# bmsSlave_conn.net
KiCad netlist of a schematic drawn in Altium Designer
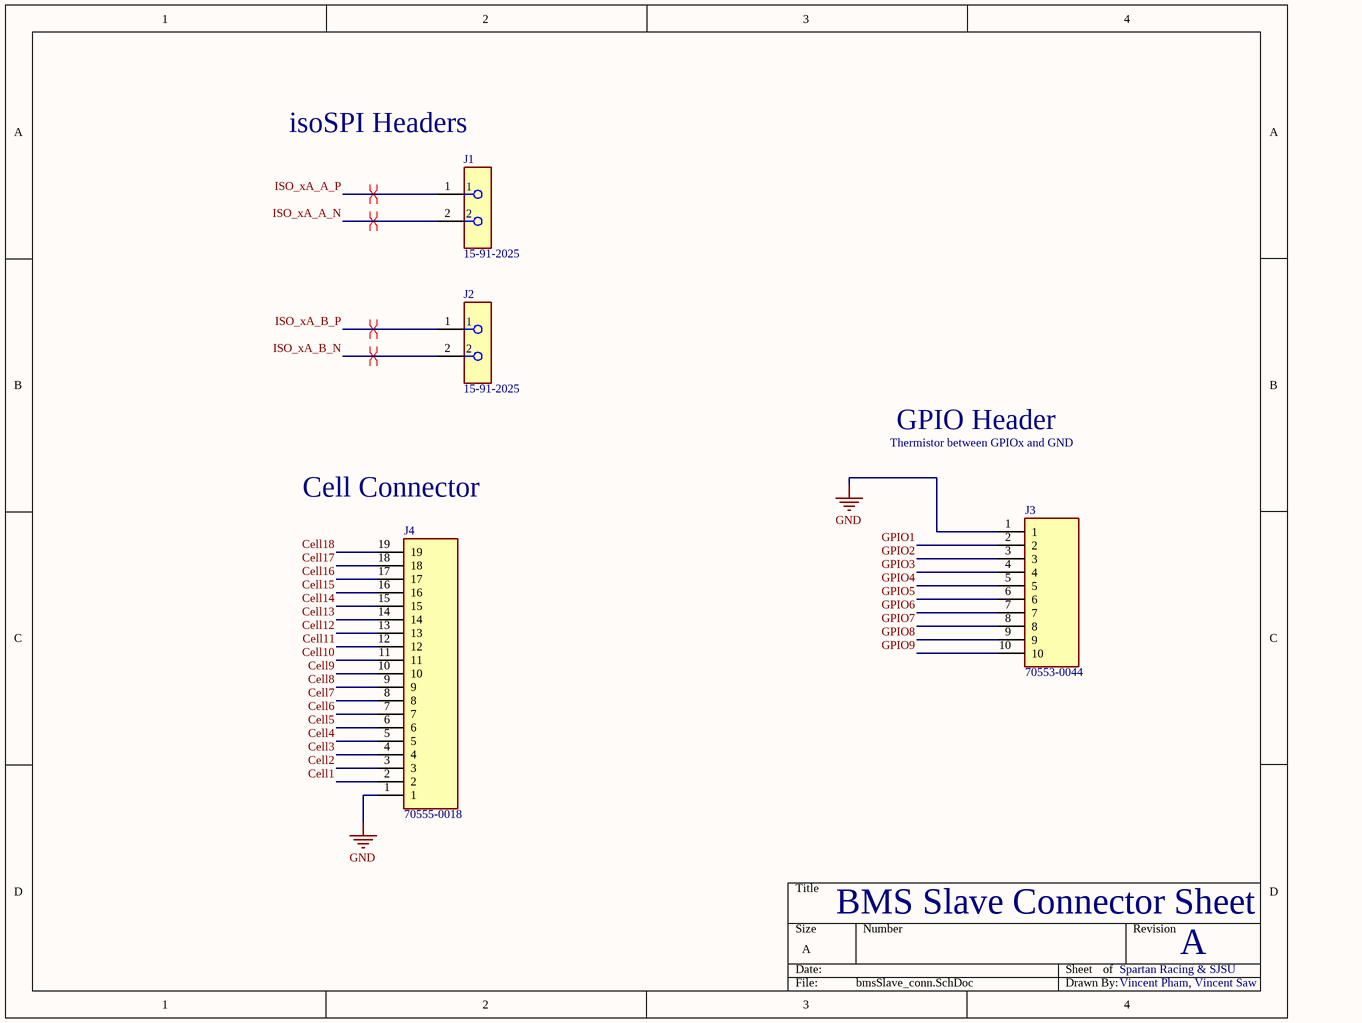
[diagram p0: bmsSlave_conn.SchDoc]

(export (version "E")
  (design (tool "Eeschema 10.0.6"))
  (components
    (comp (ref "J1")
      (value "15-91-2025")
      (footprint "FP-15-91-2025-MFG")
      (description "CONN HEADER SMD R/A 2POS 2.54MM")
      (libsource (lib "Altium Content Vault") (part "3ddab50f66188bb7952c54a1b76274c"))
    )
    (comp (ref "J2")
      (value "15-91-2025")
      (footprint "FP-15-91-2025-MFG")
      (description "CONN HEADER SMD R/A 2POS 2.54MM")
      (libsource (lib "Altium Content Vault") (part "3ddab50f66188bb7952c54a1b76274c"))
    )
    (comp (ref "J3")
      (value "70553-0044")
      (footprint "705550044")
      (description "Connector")
      (fields (field (name "MOUSER PART NUMBER") "538-70553-0044"))
      (libsource (lib "bmsSlave") (part "70553-0044"))
    )
    (comp (ref "J4")
      (value "70555-0018")
      (footprint "705550018")
      (description "Connector")
      (libsource (lib "bmsSlave") (part "70555-0018"))
    )
  )
  (nets
    (net (code "1") (name "/Cell1") (class "Default")
      (node (ref "J4") (pin "2") (pinfunction "2_2") (pintype "passive"))
    )
    (net (code "2") (name "/Cell2") (class "Default")
      (node (ref "J4") (pin "3") (pinfunction "3_3") (pintype "passive"))
    )
    (net (code "3") (name "/Cell3") (class "Default")
      (node (ref "J4") (pin "4") (pinfunction "4_4") (pintype "passive"))
    )
    (net (code "4") (name "/Cell4") (class "Default")
      (node (ref "J4") (pin "5") (pinfunction "5_5") (pintype "passive"))
    )
    (net (code "5") (name "/Cell5") (class "Default")
      (node (ref "J4") (pin "6") (pinfunction "6_6") (pintype "passive"))
    )
    (net (code "6") (name "/Cell6") (class "Default")
      (node (ref "J4") (pin "7") (pinfunction "7_7") (pintype "passive"))
    )
    (net (code "7") (name "/Cell7") (class "Default")
      (node (ref "J4") (pin "8") (pinfunction "8_8") (pintype "passive"))
    )
    (net (code "8") (name "/Cell8") (class "Default")
      (node (ref "J4") (pin "9") (pinfunction "9_9") (pintype "passive"))
    )
    (net (code "9") (name "/Cell9") (class "Default")
      (node (ref "J4") (pin "10") (pinfunction "10_10") (pintype "passive"))
    )
    (net (code "10") (name "/Cell10") (class "Default")
      (node (ref "J4") (pin "11") (pinfunction "11_11") (pintype "passive"))
    )
    (net (code "11") (name "/Cell11") (class "Default")
      (node (ref "J4") (pin "12") (pinfunction "12_12") (pintype "passive"))
    )
    (net (code "12") (name "/Cell12") (class "Default")
      (node (ref "J4") (pin "13") (pinfunction "13_13") (pintype "passive"))
    )
    (net (code "13") (name "/Cell13") (class "Default")
      (node (ref "J4") (pin "14") (pinfunction "14_14") (pintype "passive"))
    )
    (net (code "14") (name "/Cell14") (class "Default")
      (node (ref "J4") (pin "15") (pinfunction "15_15") (pintype "passive"))
    )
    (net (code "15") (name "/Cell15") (class "Default")
      (node (ref "J4") (pin "16") (pinfunction "16_16") (pintype "passive"))
    )
    (net (code "16") (name "/Cell16") (class "Default")
      (node (ref "J4") (pin "17") (pinfunction "17_17") (pintype "passive"))
    )
    (net (code "17") (name "/Cell17") (class "Default")
      (node (ref "J4") (pin "18") (pinfunction "18_18") (pintype "passive"))
    )
    (net (code "18") (name "/Cell18") (class "Default")
      (node (ref "J4") (pin "19") (pinfunction "19_19") (pintype "passive"))
    )
    (net (code "19") (name "/GPIO1") (class "Default")
      (node (ref "J3") (pin "2") (pinfunction "2_2") (pintype "passive"))
    )
    (net (code "20") (name "/GPIO2") (class "Default")
      (node (ref "J3") (pin "3") (pinfunction "3_3") (pintype "passive"))
    )
    (net (code "21") (name "/GPIO3") (class "Default")
      (node (ref "J3") (pin "4") (pinfunction "4_4") (pintype "passive"))
    )
    (net (code "22") (name "/GPIO4") (class "Default")
      (node (ref "J3") (pin "5") (pinfunction "5_5") (pintype "passive"))
    )
    (net (code "23") (name "/GPIO5") (class "Default")
      (node (ref "J3") (pin "6") (pinfunction "6_6") (pintype "passive"))
    )
    (net (code "24") (name "/GPIO6") (class "Default")
      (node (ref "J3") (pin "7") (pinfunction "7_7") (pintype "passive"))
    )
    (net (code "25") (name "/GPIO7") (class "Default")
      (node (ref "J3") (pin "8") (pinfunction "8_8") (pintype "passive"))
    )
    (net (code "26") (name "/GPIO8") (class "Default")
      (node (ref "J3") (pin "9") (pinfunction "9_9") (pintype "passive"))
    )
    (net (code "27") (name "/GPIO9") (class "Default")
      (node (ref "J3") (pin "10") (pinfunction "10_10") (pintype "passive"))
    )
    (net (code "28") (name "/ISO_xA_A_N") (class "Default")
      (node (ref "J1") (pin "2") (pinfunction "2_2") (pintype "passive"))
    )
    (net (code "29") (name "/ISO_xA_A_P") (class "Default")
      (node (ref "J1") (pin "1") (pinfunction "1_1") (pintype "passive"))
    )
    (net (code "30") (name "/ISO_xA_B_N") (class "Default")
      (node (ref "J2") (pin "2") (pinfunction "2_2") (pintype "passive"))
    )
    (net (code "31") (name "/ISO_xA_B_P") (class "Default")
      (node (ref "J2") (pin "1") (pinfunction "1_1") (pintype "passive"))
    )
    (net (code "32") (name "GND") (class "Default")
      (node (ref "J3") (pin "1") (pinfunction "1_1") (pintype "passive"))
      (node (ref "J4") (pin "1") (pinfunction "1_1") (pintype "passive"))
    )
  )
)
